# ESC.net
KiCad netlist of a schematic drawn in Altium Designer
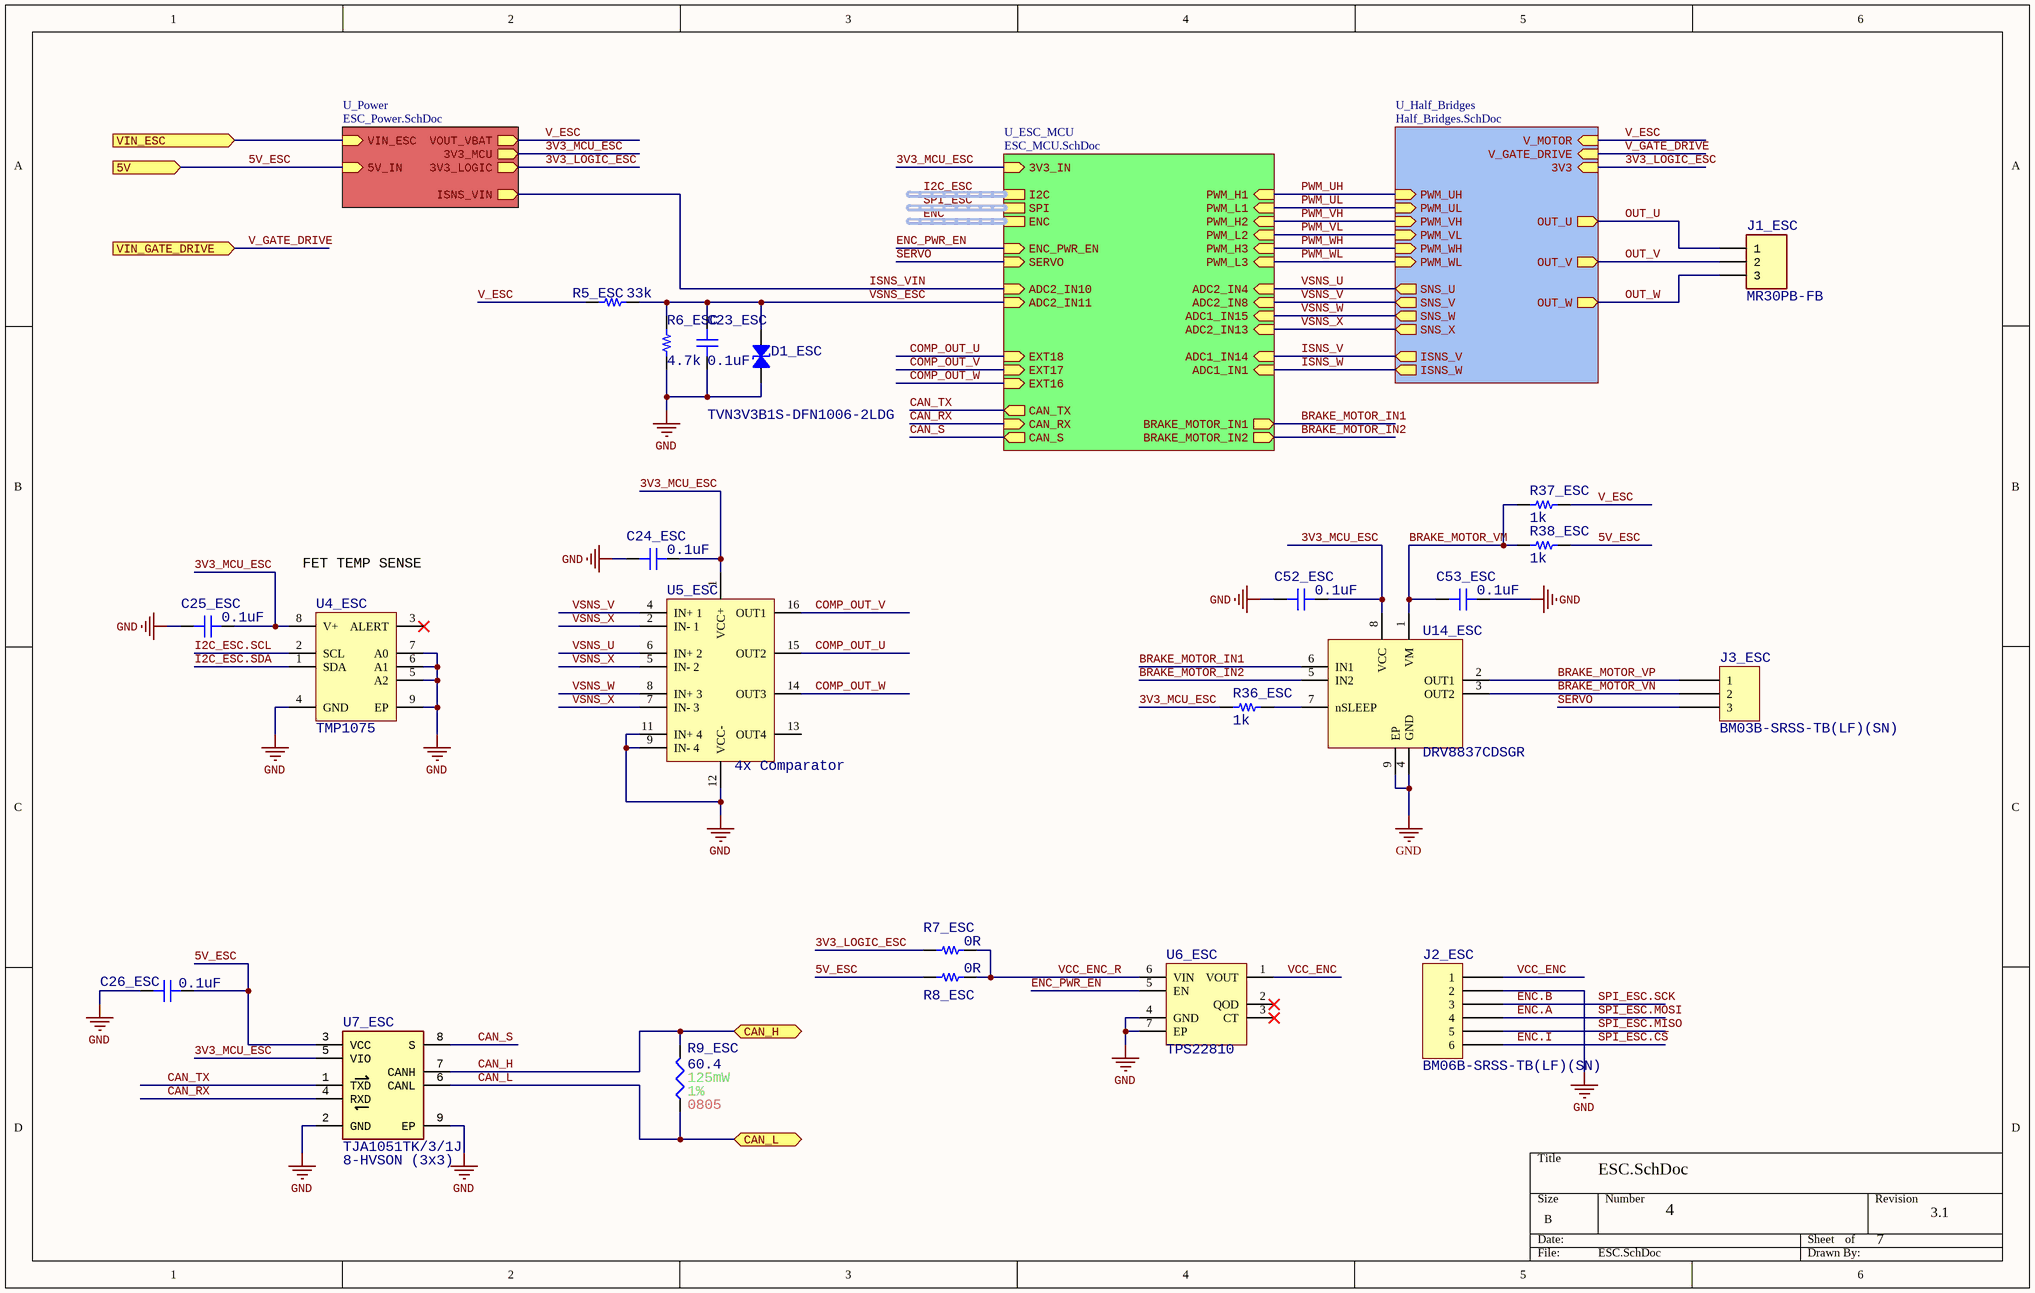
[diagram p0: ESC.SchDoc]

(export (version "E")
  (design (tool "Eeschema 10.0.6"))
  (components
    (comp (ref "C23_ESC")
      (value "0.1uF")
      (footprint "CAP_0402")
      (description "CAP CER 402")
      (libsource (lib "IC") (part "CAP_0402"))
    )
    (comp (ref "C24_ESC")
      (value "0.1uF")
      (footprint "CAP_0402")
      (description "CAP CER 402")
      (libsource (lib "IC") (part "CAP_0402"))
    )
    (comp (ref "C25_ESC")
      (value "0.1uF")
      (footprint "CAP_0402")
      (description "CAP CER 402")
      (libsource (lib "IC") (part "CAP_0402"))
    )
    (comp (ref "C26_ESC")
      (value "0.1uF")
      (footprint "CAP_0402")
      (description "CAP CER 402")
      (libsource (lib "IC") (part "CAP_0402"))
    )
    (comp (ref "C52_ESC")
      (value "0.1uF")
      (footprint "CAP_0402")
      (description "CAP CER 402")
      (libsource (lib "IC") (part "CAP_0402"))
    )
    (comp (ref "C53_ESC")
      (value "0.1uF")
      (footprint "CAP_0402")
      (description "CAP CER 402")
      (libsource (lib "IC") (part "CAP_0402"))
    )
    (comp (ref "D1_ESC")
      (value "TVN3V3B1S-DFN1006-2LDG")
      (footprint "0402")
      (description "TVS DIODE 3.3V 14.2PF DFN1006")
      (fields (field (name "MANUFACTURER") "INPAQ Technology Co., Ltd"))
      (libsource (lib "Celestial Altium Library - altium_library") (part "Diode TVS"))
    )
    (comp (ref "J1_ESC")
      (value "MR30PB-FB")
      (footprint "MR30PB-F")
      (description "Vertical 3 pin barrel connector")
      (fields (field (name "MANUFACTURER") "Amass"))
      (libsource (lib "Raise Robotics") (part "MR30PB-FB"))
    )
    (comp (ref "J2_ESC")
      (value "BM06B-SRSS-TB(LF)(SN)")
      (footprint "JST BM06B-SRSS-TB")
      (description "CONN HEADER SMD 6POS 1MM")
      (fields (field (name "MANUFACTURER") "JST Sales America Inc."))
      (libsource (lib "Celestial Altium Library - altium_library") (part "6 Pin"))
    )
    (comp (ref "J3_ESC")
      (value "BM03B-SRSS-TB(LF)(SN)")
      (footprint "JST BM03B-SRSS-TB")
      (description "CONN HEADER SMD 3POS 1MM")
      (fields (field (name "MANUFACTURER") "JST Sales America Inc."))
      (libsource (lib "Celestial Altium Library - altium_library") (part "3 Pin"))
    )
    (comp (ref "R5_ESC")
      (value "33k")
      (footprint "RES_0402")
      (description "RES 0402")
      (libsource (lib "IC") (part "RES_0402"))
    )
    (comp (ref "R6_ESC")
      (value "4.7k")
      (footprint "RES_0402")
      (description "RES 0402")
      (libsource (lib "IC") (part "RES_0402"))
    )
    (comp (ref "R7_ESC")
      (value "0R")
      (footprint "RES_0402")
      (description "RES 0402")
      (libsource (lib "IC") (part "RES_0402"))
    )
    (comp (ref "R8_ESC")
      (value "0R")
      (footprint "RES_0402")
      (description "RES 0402")
      (libsource (lib "IC") (part "RES_0402"))
    )
    (comp (ref "R9_ESC")
      (value "60.4")
      (footprint "0805 Resistor")
      (description "Res 60.4 Ohm 1% 1/8W 0805")
      (fields
        (field (name "POWER") "125mW")
        (field (name "TOLERANCE") "1%")
        (field (name "CASE/PACKAGE") "0805")
        (field (name "MANUFACTURER PART NUMBER") "TFA0805R60R4F-T5")
      )
      (libsource (lib "Raise Robotics") (part "Resistor"))
    )
    (comp (ref "R36_ESC")
      (value "1k")
      (footprint "RES_0402")
      (description "RES 0402")
      (libsource (lib "IC") (part "RES_0402"))
    )
    (comp (ref "R37_ESC")
      (value "1k")
      (footprint "RES_0402")
      (description "RES 0402")
      (libsource (lib "IC") (part "RES_0402"))
    )
    (comp (ref "R38_ESC")
      (value "1k")
      (footprint "RES_0402")
      (description "RES 0402")
      (libsource (lib "IC") (part "RES_0402"))
    )
    (comp (ref "U4_ESC")
      (value "TMP1075")
      (footprint "8-WSON_2x2_0.5mm")
      (description "I2C TEMP SENSOR")
      (libsource (lib "IC") (part "TMP1075"))
    )
    (comp (ref "U5_ESC")
      (value "4x Comparator")
      (footprint "QFN50P300X300X100-16N")
      (description "Comparator General Purpose CMOS, DTL, MOS, Open-Collector, TTL 16-QFN (3x3)")
      (libsource (lib "IC") (part "LM2901Q4T"))
    )
    (comp (ref "U6_ESC")
      (value "TPS22810")
      (footprint "6-WSON_2x2_0.65mm")
      (description "Load switch TPS22810DRVR")
      (libsource (lib "IC") (part "TPS22810DRVR"))
    )
    (comp (ref "U7_ESC")
      (value "TJA1051TK/3/1J")
      (footprint "TJA1044xxK")
      (description "Interface Circuit, PDSO8")
      (fields (field (name "CASE/PACKAGE") "8-HVSON (3x3)"))
      (libsource (lib "Raise Robotics") (part "TJA1044"))
    )
    (comp (ref "U14_ESC")
      (value "DRV8837CDSGR")
      (footprint "SON50P200X200X80-9N")
      (description "11-V, 1-A H-bridge motor driver 8-WSON -40 to 85")
      (fields (field (name "MF") "Texas Instruments"))
      (libsource (lib "IC") (part "DRV8837CDSGR"))
    )
  )
  (nets
    (net (code "4") (name "/3V3_LOGIC_ESC") (class "Default")
      (node (ref "R7_ESC") (pin "2") (pinfunction "2_2") (pintype "passive"))
    )
    (net (code "5") (name "/3V3_MCU_ESC") (class "Default")
      (node (ref "C24_ESC") (pin "2") (pinfunction "2_2") (pintype "passive"))
      (node (ref "C25_ESC") (pin "2") (pinfunction "2_2") (pintype "passive"))
      (node (ref "C52_ESC") (pin "2") (pinfunction "2_2") (pintype "passive"))
      (node (ref "R36_ESC") (pin "1") (pinfunction "1_1") (pintype "passive"))
      (node (ref "U14_ESC") (pin "8") (pinfunction "VCC_8") (pintype "passive"))
      (node (ref "U4_ESC") (pin "8") (pinfunction "V+_8") (pintype "passive"))
      (node (ref "U5_ESC") (pin "1") (pinfunction "VCC+_1") (pintype "passive"))
      (node (ref "U7_ESC") (pin "5") (pinfunction "VIO_5") (pintype "passive"))
    )
    (net (code "6") (name "/5V_ESC") (class "Default")
      (node (ref "C26_ESC") (pin "1") (pinfunction "1_1") (pintype "passive"))
      (node (ref "R38_ESC") (pin "2") (pinfunction "2_2") (pintype "passive"))
      (node (ref "R8_ESC") (pin "2") (pinfunction "2_2") (pintype "passive"))
      (node (ref "U7_ESC") (pin "3") (pinfunction "VCC_3") (pintype "passive"))
    )
    (net (code "7") (name "/BRAKE_MOTOR_IN1") (class "Default")
      (node (ref "U14_ESC") (pin "6") (pinfunction "IN1_6") (pintype "passive"))
    )
    (net (code "8") (name "/BRAKE_MOTOR_IN2") (class "Default")
      (node (ref "U14_ESC") (pin "5") (pinfunction "IN2_5") (pintype "passive"))
    )
    (net (code "9") (name "/BRAKE_MOTOR_VM") (class "Default")
      (node (ref "C53_ESC") (pin "1") (pinfunction "1_1") (pintype "passive"))
      (node (ref "R37_ESC") (pin "1") (pinfunction "1_1") (pintype "passive"))
      (node (ref "R38_ESC") (pin "1") (pinfunction "1_1") (pintype "passive"))
      (node (ref "U14_ESC") (pin "1") (pinfunction "VM_1") (pintype "passive"))
    )
    (net (code "10") (name "/BRAKE_MOTOR_VN") (class "Default")
      (node (ref "J3_ESC") (pin "2") (pinfunction "2_2") (pintype "passive"))
      (node (ref "U14_ESC") (pin "3") (pinfunction "OUT2_3") (pintype "passive"))
    )
    (net (code "11") (name "/BRAKE_MOTOR_VP") (class "Default")
      (node (ref "J3_ESC") (pin "1") (pinfunction "1_1") (pintype "passive"))
      (node (ref "U14_ESC") (pin "2") (pinfunction "OUT1_2") (pintype "passive"))
    )
    (net (code "12") (name "/CAN_H") (class "Default")
      (node (ref "R9_ESC") (pin "2") (pinfunction "2_2") (pintype "passive"))
      (node (ref "U7_ESC") (pin "7") (pinfunction "CANH_7") (pintype "passive"))
    )
    (net (code "13") (name "/CAN_L") (class "Default")
      (node (ref "R9_ESC") (pin "1") (pinfunction "1_1") (pintype "passive"))
      (node (ref "U7_ESC") (pin "6") (pinfunction "CANL_6") (pintype "passive"))
    )
    (net (code "14") (name "/CAN_RX") (class "Default")
      (node (ref "U7_ESC") (pin "4") (pinfunction "RXD_4") (pintype "passive"))
    )
    (net (code "15") (name "/CAN_S") (class "Default")
      (node (ref "U7_ESC") (pin "8") (pinfunction "S_8") (pintype "passive"))
    )
    (net (code "16") (name "/CAN_TX") (class "Default")
      (node (ref "U7_ESC") (pin "1") (pinfunction "TXD_1") (pintype "passive"))
    )
    (net (code "17") (name "/COMP_OUT_U") (class "Default")
      (node (ref "U5_ESC") (pin "15") (pinfunction "OUT2_15") (pintype "passive"))
    )
    (net (code "18") (name "/COMP_OUT_V") (class "Default")
      (node (ref "U5_ESC") (pin "16") (pinfunction "OUT1_16") (pintype "passive"))
    )
    (net (code "19") (name "/COMP_OUT_W") (class "Default")
      (node (ref "U5_ESC") (pin "14") (pinfunction "OUT3_14") (pintype "passive"))
    )
    (net (code "20") (name "/ENC.A") (class "Default")
      (node (ref "J2_ESC") (pin "4") (pinfunction "4_4") (pintype "passive"))
    )
    (net (code "21") (name "/ENC.B") (class "Default")
      (node (ref "J2_ESC") (pin "3") (pinfunction "3_3") (pintype "passive"))
    )
    (net (code "22") (name "/ENC.I") (class "Default")
      (node (ref "J2_ESC") (pin "6") (pinfunction "6_6") (pintype "passive"))
    )
    (net (code "23") (name "/ENC_PWR_EN") (class "Default")
      (node (ref "U6_ESC") (pin "5") (pinfunction "EN_5") (pintype "passive"))
    )
    (net (code "24") (name "/I2C_ESC.SCL") (class "Default")
      (node (ref "U4_ESC") (pin "2") (pinfunction "SCL_2") (pintype "passive"))
    )
    (net (code "25") (name "/I2C_ESC.SDA") (class "Default")
      (node (ref "U4_ESC") (pin "1") (pinfunction "SDA_1") (pintype "passive"))
    )
    (net (code "29") (name "/OUT_U") (class "Default")
      (node (ref "J1_ESC") (pin "1") (pinfunction "1_1") (pintype "passive"))
    )
    (net (code "30") (name "/OUT_V") (class "Default")
      (node (ref "J1_ESC") (pin "2") (pinfunction "2_2") (pintype "passive"))
    )
    (net (code "31") (name "/OUT_W") (class "Default")
      (node (ref "J1_ESC") (pin "3") (pinfunction "3_3") (pintype "passive"))
    )
    (net (code "38") (name "/SERVO") (class "Default")
      (node (ref "J3_ESC") (pin "3") (pinfunction "3_3") (pintype "passive"))
    )
    (net (code "39") (name "/SPI_ESC.MISO") (class "Default")
      (node (ref "J2_ESC") (pin "5") (pinfunction "5_5") (pintype "passive"))
    )
    (net (code "40") (name "/VCC_ENC") (class "Default")
      (node (ref "J2_ESC") (pin "1") (pinfunction "1_1") (pintype "passive"))
      (node (ref "U6_ESC") (pin "1") (pinfunction "VOUT_1") (pintype "passive"))
    )
    (net (code "41") (name "/VCC_ENC_R") (class "Default")
      (node (ref "R7_ESC") (pin "1") (pinfunction "1_1") (pintype "passive"))
      (node (ref "R8_ESC") (pin "1") (pinfunction "1_1") (pintype "passive"))
      (node (ref "U6_ESC") (pin "6") (pinfunction "VIN_6") (pintype "passive"))
    )
    (net (code "43") (name "/VSNS_ESC") (class "Default")
      (node (ref "C23_ESC") (pin "2") (pinfunction "2_2") (pintype "passive"))
      (node (ref "D1_ESC") (pin "2") (pinfunction "2_2") (pintype "passive"))
      (node (ref "R5_ESC") (pin "1") (pinfunction "1_1") (pintype "passive"))
      (node (ref "R6_ESC") (pin "1") (pinfunction "1_1") (pintype "passive"))
    )
    (net (code "44") (name "/VSNS_U") (class "Default")
      (node (ref "U5_ESC") (pin "6") (pinfunction "IN+_2_6") (pintype "passive"))
    )
    (net (code "45") (name "/VSNS_V") (class "Default")
      (node (ref "U5_ESC") (pin "4") (pinfunction "IN+_1_4") (pintype "passive"))
    )
    (net (code "46") (name "/VSNS_W") (class "Default")
      (node (ref "U5_ESC") (pin "8") (pinfunction "IN+_3_8") (pintype "passive"))
    )
    (net (code "47") (name "/VSNS_X") (class "Default")
      (node (ref "U5_ESC") (pin "2") (pinfunction "IN-_1_2") (pintype "passive"))
      (node (ref "U5_ESC") (pin "5") (pinfunction "IN-_2_5") (pintype "passive"))
      (node (ref "U5_ESC") (pin "7") (pinfunction "IN-_3_7") (pintype "passive"))
    )
    (net (code "48") (name "/V_ESC") (class "Default")
      (node (ref "R37_ESC") (pin "2") (pinfunction "2_2") (pintype "passive"))
      (node (ref "R5_ESC") (pin "2") (pinfunction "2_2") (pintype "passive"))
    )
    (net (code "53") (name "GND") (class "Default")
      (node (ref "C23_ESC") (pin "1") (pinfunction "1_1") (pintype "passive"))
      (node (ref "C24_ESC") (pin "1") (pinfunction "1_1") (pintype "passive"))
      (node (ref "C25_ESC") (pin "1") (pinfunction "1_1") (pintype "passive"))
      (node (ref "C26_ESC") (pin "2") (pinfunction "2_2") (pintype "passive"))
      (node (ref "C52_ESC") (pin "1") (pinfunction "1_1") (pintype "passive"))
      (node (ref "C53_ESC") (pin "2") (pinfunction "2_2") (pintype "passive"))
      (node (ref "D1_ESC") (pin "1") (pinfunction "1_1") (pintype "passive"))
      (node (ref "J2_ESC") (pin "2") (pinfunction "2_2") (pintype "passive"))
      (node (ref "R6_ESC") (pin "2") (pinfunction "2_2") (pintype "passive"))
      (node (ref "U14_ESC") (pin "4") (pinfunction "GND_4") (pintype "passive"))
      (node (ref "U14_ESC") (pin "9") (pinfunction "EP_9") (pintype "passive"))
      (node (ref "U4_ESC") (pin "4") (pinfunction "GND_4") (pintype "passive"))
      (node (ref "U4_ESC") (pin "5") (pinfunction "A2_5") (pintype "passive"))
      (node (ref "U4_ESC") (pin "6") (pinfunction "A1_6") (pintype "passive"))
      (node (ref "U4_ESC") (pin "7") (pinfunction "A0_7") (pintype "passive"))
      (node (ref "U4_ESC") (pin "9") (pinfunction "EP_9") (pintype "passive"))
      (node (ref "U5_ESC") (pin "11") (pinfunction "IN+_4_11") (pintype "passive"))
      (node (ref "U5_ESC") (pin "12") (pinfunction "VCC-_12") (pintype "passive"))
      (node (ref "U5_ESC") (pin "9") (pinfunction "IN-_4_9") (pintype "passive"))
      (node (ref "U6_ESC") (pin "4") (pinfunction "GND_4") (pintype "passive"))
      (node (ref "U6_ESC") (pin "7") (pinfunction "EP_7") (pintype "passive"))
      (node (ref "U7_ESC") (pin "2") (pinfunction "GND_2") (pintype "passive"))
      (node (ref "U7_ESC") (pin "9") (pinfunction "EP_9") (pintype "passive"))
    )
    (net (code "54") (name "Net-(U14_ESC-nSLEEP)") (class "Default")
      (node (ref "R36_ESC") (pin "2") (pinfunction "2_2") (pintype "passive"))
      (node (ref "U14_ESC") (pin "7") (pinfunction "nSLEEP_7") (pintype "passive"))
    )
    (net (code "55") (name "unconnected-(U4_ESC-ALERT-Pad3)") (class "Default")
      (node (ref "U4_ESC") (pin "3") (pinfunction "ALERT_3") (pintype "passive+no_connect"))
    )
    (net (code "56") (name "unconnected-(U5_ESC-OUT4-Pad13)") (class "Default")
      (node (ref "U5_ESC") (pin "13") (pinfunction "OUT4_13") (pintype "passive"))
    )
    (net (code "57") (name "unconnected-(U6_ESC-CT-Pad3)") (class "Default")
      (node (ref "U6_ESC") (pin "3") (pinfunction "CT_3") (pintype "passive+no_connect"))
    )
    (net (code "58") (name "unconnected-(U6_ESC-QOD-Pad2)") (class "Default")
      (node (ref "U6_ESC") (pin "2") (pinfunction "QOD_2") (pintype "passive+no_connect"))
    )
  )
)
